# Puzzle_LED_Strip_driver.net
KiCad netlist of a schematic drawn in EAGLE
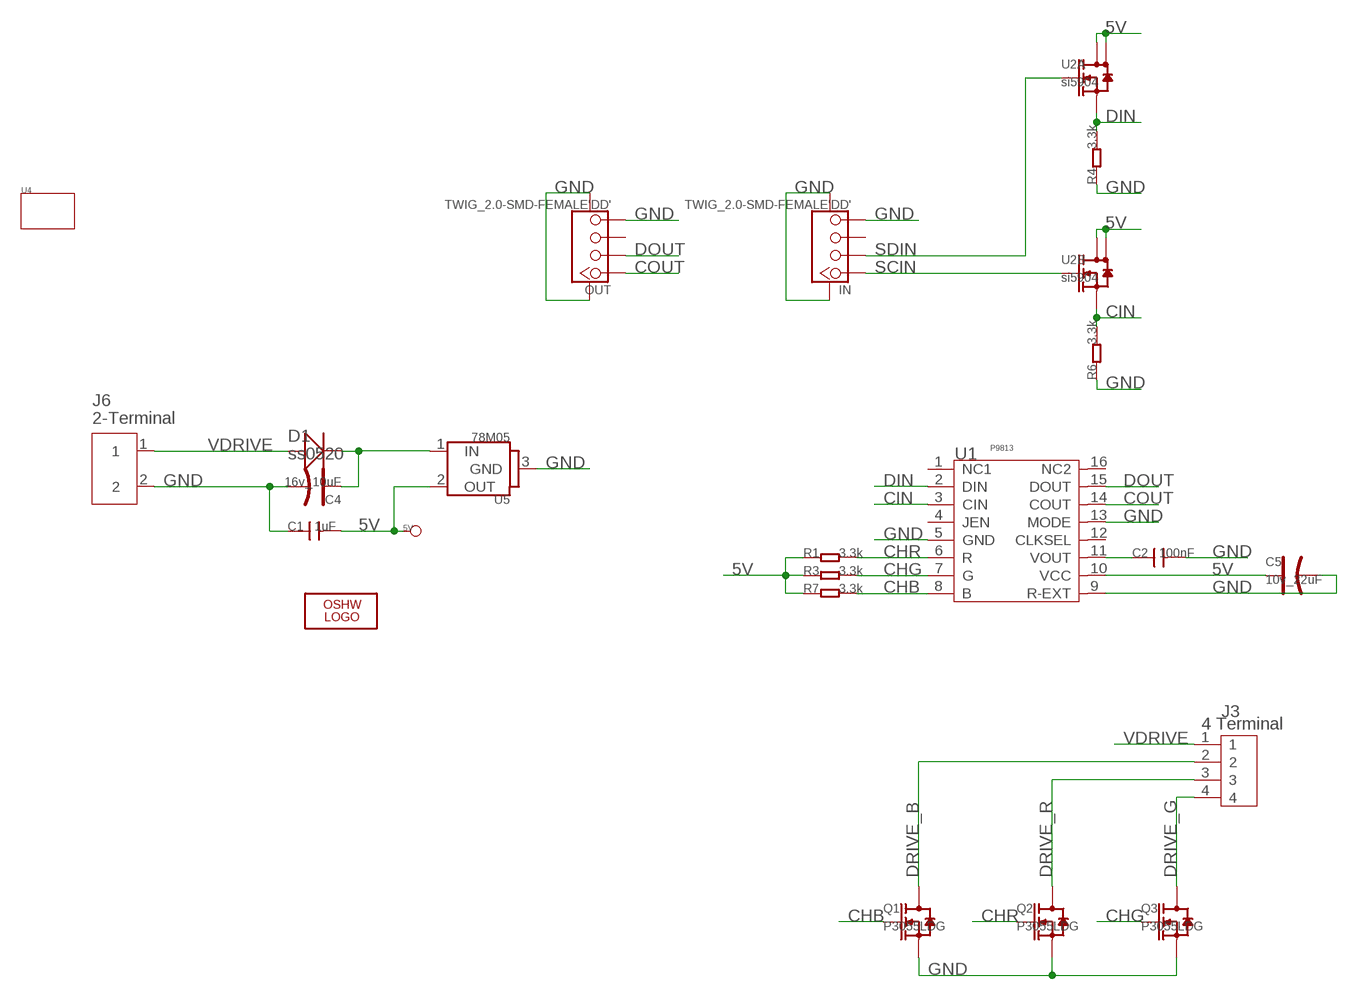
[diagram p0: schematic, sheet 1]

(export (version "E")
  (design (tool "Eeschema 10.0.6"))
  (components
    (comp (ref "5V")
      (value "DNP")
      (footprint "eagle-import:TP_3535")
      (libsource (lib "eagle-import") (part "PAD-TEST-POINT-CIRCLE_SIZE_3030"))
    )
    (comp (ref "C1")
      (value "1uF")
      (footprint "eagle-import:0805")
      (libsource (lib "eagle-import") (part "C-0805"))
    )
    (comp (ref "C2")
      (value "100nF")
      (footprint "eagle-import:0402")
      (libsource (lib "eagle-import") (part "C-0402"))
    )
    (comp (ref "C4")
      (value "16v_10uF")
      (footprint "eagle-import:AVX-A")
      (libsource (lib "eagle-import") (part "CAP-AVX-A"))
    )
    (comp (ref "C5")
      (value "10v_22uF")
      (footprint "eagle-import:AVX-A")
      (libsource (lib "eagle-import") (part "CAP-AVX-A"))
    )
    (comp (ref "D1")
      (value "ss0520")
      (footprint "eagle-import:SOD123")
      (libsource (lib "eagle-import") (part "D'1206'"))
    )
    (comp (ref "IN")
      (value "TWIG_2.0-SMD-FEMALE'DD'")
      (footprint "eagle-import:2.0_1X4DD")
      (libsource (lib "eagle-import") (part "TWIG_2.0-SMD-FEMALE'DD'"))
    )
    (comp (ref "J3")
      (value "4 Terminal")
      (footprint "eagle-import:4P-3.36")
      (libsource (lib "eagle-import") (part "SCREW-TERMINAL-4P'3.36'"))
    )
    (comp (ref "J6")
      (value "2-Terminal")
      (footprint "eagle-import:2P-3.36")
      (libsource (lib "eagle-import") (part "SCREW-TERMINAL-2P3.36"))
    )
    (comp (ref "LOGO1")
      (value "LOGO-OSHW-FILLX0200-NT")
      (footprint "eagle-import:OSHW_FILLX200_NOTEXT")
      (libsource (lib "eagle-import") (part "LOGO-OSHW-FILLX0200-NT"))
    )
    (comp (ref "OUT")
      (value "TWIG_2.0-SMD-FEMALE'DD'")
      (footprint "eagle-import:2.0_1X4DD")
      (libsource (lib "eagle-import") (part "TWIG_2.0-SMD-FEMALE'DD'"))
    )
    (comp (ref "Q1")
      (value "P3055LDG")
      (footprint "eagle-import:TO252")
      (libsource (lib "eagle-import") (part "MOSFET-N-P3055LDG"))
    )
    (comp (ref "Q2")
      (value "P3055LDG")
      (footprint "eagle-import:TO252")
      (libsource (lib "eagle-import") (part "MOSFET-N-P3055LDG"))
    )
    (comp (ref "Q3")
      (value "P3055LDG")
      (footprint "eagle-import:TO252")
      (libsource (lib "eagle-import") (part "MOSFET-N-P3055LDG"))
    )
    (comp (ref "R1")
      (value "3.3k")
      (footprint "eagle-import:0402")
      (libsource (lib "eagle-import") (part "R-0402"))
    )
    (comp (ref "R3")
      (value "3.3k")
      (footprint "eagle-import:0402")
      (libsource (lib "eagle-import") (part "R-0402"))
    )
    (comp (ref "R4")
      (value "3.3k")
      (footprint "eagle-import:0402")
      (libsource (lib "eagle-import") (part "R-0402"))
    )
    (comp (ref "R6")
      (value "3.3k")
      (footprint "eagle-import:0402")
      (libsource (lib "eagle-import") (part "R-0402"))
    )
    (comp (ref "R7")
      (value "3.3k")
      (footprint "eagle-import:0402")
      (libsource (lib "eagle-import") (part "R-0402"))
    )
    (comp (ref "U1")
      (value "P9813")
      (footprint "eagle-import:SSOP16")
      (libsource (lib "eagle-import") (part "P9813-SSOP16"))
    )
    (comp (ref "U2")
      (value "si5904")
      (footprint "eagle-import:1206-8")
      (libsource (lib "eagle-import") (part "MOSFET-DUAL-N-1206-8"))
    )
    (comp (ref "U4")
      (value "TWIG3U-W/O-DRILL")
      (footprint "eagle-import:3U-DIM-W_O-DRILL")
      (libsource (lib "eagle-import") (part "TWIG3U-W/O-DRILL"))
    )
    (comp (ref "U5")
      (value "78M05")
      (footprint "eagle-import:TO252")
      (libsource (lib "eagle-import") (part "78M05-TO252"))
    )
  )
  (nets
    (net (code "1") (name "/5V") (class "Default")
      (node (ref "5V") (pin "T") (pinfunction "T_T") (pintype "bidirectional"))
      (node (ref "C1") (pin "2") (pinfunction "2_2") (pintype "passive"))
      (node (ref "C5") (pin "+") (pinfunction "+_+") (pintype "passive"))
      (node (ref "R1") (pin "1") (pinfunction "1_1") (pintype "passive"))
      (node (ref "R3") (pin "1") (pinfunction "1_1") (pintype "passive"))
      (node (ref "R7") (pin "1") (pinfunction "1_1") (pintype "passive"))
      (node (ref "U1") (pin "10") (pinfunction "VCC_10") (pintype "power_in"))
      (node (ref "U2") (pin "5") (pinfunction "D_5") (pintype "passive"))
      (node (ref "U2") (pin "6") (pinfunction "D_6") (pintype "passive"))
      (node (ref "U2") (pin "7") (pinfunction "D_7") (pintype "passive"))
      (node (ref "U2") (pin "8") (pinfunction "D_8") (pintype "passive"))
      (node (ref "U5") (pin "2") (pinfunction "OUT_2") (pintype "bidirectional"))
    )
    (net (code "2") (name "/CHB") (class "Default")
      (node (ref "Q1") (pin "1") (pinfunction "G_1") (pintype "passive"))
      (node (ref "R7") (pin "2") (pinfunction "2_2") (pintype "passive"))
      (node (ref "U1") (pin "8") (pinfunction "B_8") (pintype "output"))
    )
    (net (code "3") (name "/CHG") (class "Default")
      (node (ref "Q3") (pin "1") (pinfunction "G_1") (pintype "passive"))
      (node (ref "R3") (pin "2") (pinfunction "2_2") (pintype "passive"))
      (node (ref "U1") (pin "7") (pinfunction "G_7") (pintype "output"))
    )
    (net (code "4") (name "/CHR") (class "Default")
      (node (ref "Q2") (pin "1") (pinfunction "G_1") (pintype "passive"))
      (node (ref "R1") (pin "2") (pinfunction "2_2") (pintype "passive"))
      (node (ref "U1") (pin "6") (pinfunction "R_6") (pintype "output"))
    )
    (net (code "5") (name "/CIN") (class "Default")
      (node (ref "R6") (pin "2") (pinfunction "2_2") (pintype "passive"))
      (node (ref "U1") (pin "3") (pinfunction "CIN_3") (pintype "input"))
      (node (ref "U2") (pin "3") (pinfunction "S_3") (pintype "passive"))
    )
    (net (code "6") (name "/COUT") (class "Default")
      (node (ref "OUT") (pin "1") (pinfunction "1_1") (pintype "bidirectional"))
      (node (ref "U1") (pin "14") (pinfunction "COUT_14") (pintype "output"))
    )
    (net (code "7") (name "/DIN") (class "Default")
      (node (ref "R4") (pin "2") (pinfunction "2_2") (pintype "passive"))
      (node (ref "U1") (pin "2") (pinfunction "DIN_2") (pintype "input"))
      (node (ref "U2") (pin "1") (pinfunction "S_1") (pintype "passive"))
    )
    (net (code "8") (name "/DOUT") (class "Default")
      (node (ref "OUT") (pin "2") (pinfunction "2_2") (pintype "bidirectional"))
      (node (ref "U1") (pin "15") (pinfunction "DOUT_15") (pintype "output"))
    )
    (net (code "9") (name "/DRIVE_B") (class "Default")
      (node (ref "J3") (pin "2") (pinfunction "2_2") (pintype "bidirectional"))
      (node (ref "Q1") (pin "2") (pinfunction "D_2") (pintype "passive"))
    )
    (net (code "10") (name "/DRIVE_G") (class "Default")
      (node (ref "J3") (pin "4") (pinfunction "4_4") (pintype "bidirectional"))
      (node (ref "Q3") (pin "2") (pinfunction "D_2") (pintype "passive"))
    )
    (net (code "11") (name "/DRIVE_R") (class "Default")
      (node (ref "J3") (pin "3") (pinfunction "3_3") (pintype "bidirectional"))
      (node (ref "Q2") (pin "2") (pinfunction "D_2") (pintype "passive"))
    )
    (net (code "12") (name "/GND") (class "Default")
      (node (ref "C1") (pin "1") (pinfunction "1_1") (pintype "passive"))
      (node (ref "C2") (pin "2") (pinfunction "2_2") (pintype "passive"))
      (node (ref "C4") (pin "-") (pinfunction "-_-") (pintype "passive"))
      (node (ref "C5") (pin "-") (pinfunction "-_-") (pintype "passive"))
      (node (ref "IN") (pin "4") (pinfunction "4_4") (pintype "bidirectional"))
      (node (ref "IN") (pin "SS1") (pinfunction "SS1_SS1") (pintype "bidirectional"))
      (node (ref "IN") (pin "SS2") (pinfunction "SS2_SS2") (pintype "bidirectional"))
      (node (ref "J6") (pin "2") (pinfunction "2_2") (pintype "bidirectional"))
      (node (ref "OUT") (pin "4") (pinfunction "4_4") (pintype "bidirectional"))
      (node (ref "OUT") (pin "SS1") (pinfunction "SS1_SS1") (pintype "bidirectional"))
      (node (ref "OUT") (pin "SS2") (pinfunction "SS2_SS2") (pintype "bidirectional"))
      (node (ref "Q1") (pin "3") (pinfunction "S_3") (pintype "passive"))
      (node (ref "Q2") (pin "3") (pinfunction "S_3") (pintype "passive"))
      (node (ref "Q3") (pin "3") (pinfunction "S_3") (pintype "passive"))
      (node (ref "R4") (pin "1") (pinfunction "1_1") (pintype "passive"))
      (node (ref "R6") (pin "1") (pinfunction "1_1") (pintype "passive"))
      (node (ref "U1") (pin "13") (pinfunction "MODE_13") (pintype "input"))
      (node (ref "U1") (pin "5") (pinfunction "GND_5") (pintype "power_in"))
      (node (ref "U1") (pin "9") (pinfunction "R-EXT_9") (pintype "input"))
      (node (ref "U5") (pin "3") (pinfunction "GND_3") (pintype "bidirectional"))
    )
    (net (code "13") (name "/SCIN") (class "Default")
      (node (ref "IN") (pin "1") (pinfunction "1_1") (pintype "bidirectional"))
      (node (ref "U2") (pin "4") (pinfunction "G_4") (pintype "passive"))
    )
    (net (code "14") (name "/SDIN") (class "Default")
      (node (ref "IN") (pin "2") (pinfunction "2_2") (pintype "bidirectional"))
      (node (ref "U2") (pin "2") (pinfunction "G_2") (pintype "passive"))
    )
    (net (code "15") (name "/VDRIVE") (class "Default")
      (node (ref "D1") (pin "+") (pinfunction "+_+") (pintype "passive"))
      (node (ref "J3") (pin "1") (pinfunction "1_1") (pintype "bidirectional"))
      (node (ref "J6") (pin "1") (pinfunction "1_1") (pintype "bidirectional"))
    )
    (net (code "16") (name "Net-(U1-VOUT)") (class "Default")
      (node (ref "C2") (pin "1") (pinfunction "1_1") (pintype "passive"))
      (node (ref "U1") (pin "11") (pinfunction "VOUT_11") (pintype "output"))
    )
    (net (code "17") (name "Net-(U5-IN)") (class "Default")
      (node (ref "C4") (pin "+") (pinfunction "+_+") (pintype "passive"))
      (node (ref "D1") (pin "-") (pinfunction "-_-") (pintype "passive"))
      (node (ref "U5") (pin "1") (pinfunction "IN_1") (pintype "bidirectional"))
    )
    (net (code "18") (name "unconnected-(IN-Pad3)") (class "Default")
      (node (ref "IN") (pin "3") (pinfunction "3_3") (pintype "bidirectional"))
    )
    (net (code "19") (name "unconnected-(OUT-Pad3)") (class "Default")
      (node (ref "OUT") (pin "3") (pinfunction "3_3") (pintype "bidirectional"))
    )
    (net (code "20") (name "unconnected-(U1-CLKSEL-Pad12)") (class "Default")
      (node (ref "U1") (pin "12") (pinfunction "CLKSEL_12") (pintype "input"))
    )
    (net (code "21") (name "unconnected-(U1-JEN-Pad4)") (class "Default")
      (node (ref "U1") (pin "4") (pinfunction "JEN_4") (pintype "input"))
    )
    (net (code "22") (name "unconnected-(U1-NC1-Pad1)") (class "Default")
      (node (ref "U1") (pin "1") (pinfunction "NC1_1") (pintype "no_connect"))
    )
    (net (code "23") (name "unconnected-(U1-NC2-Pad16)") (class "Default")
      (node (ref "U1") (pin "16") (pinfunction "NC2_16") (pintype "no_connect"))
    )
  )
)
